# schematic.net
KiCad netlist of a schematic drawn in EAGLE
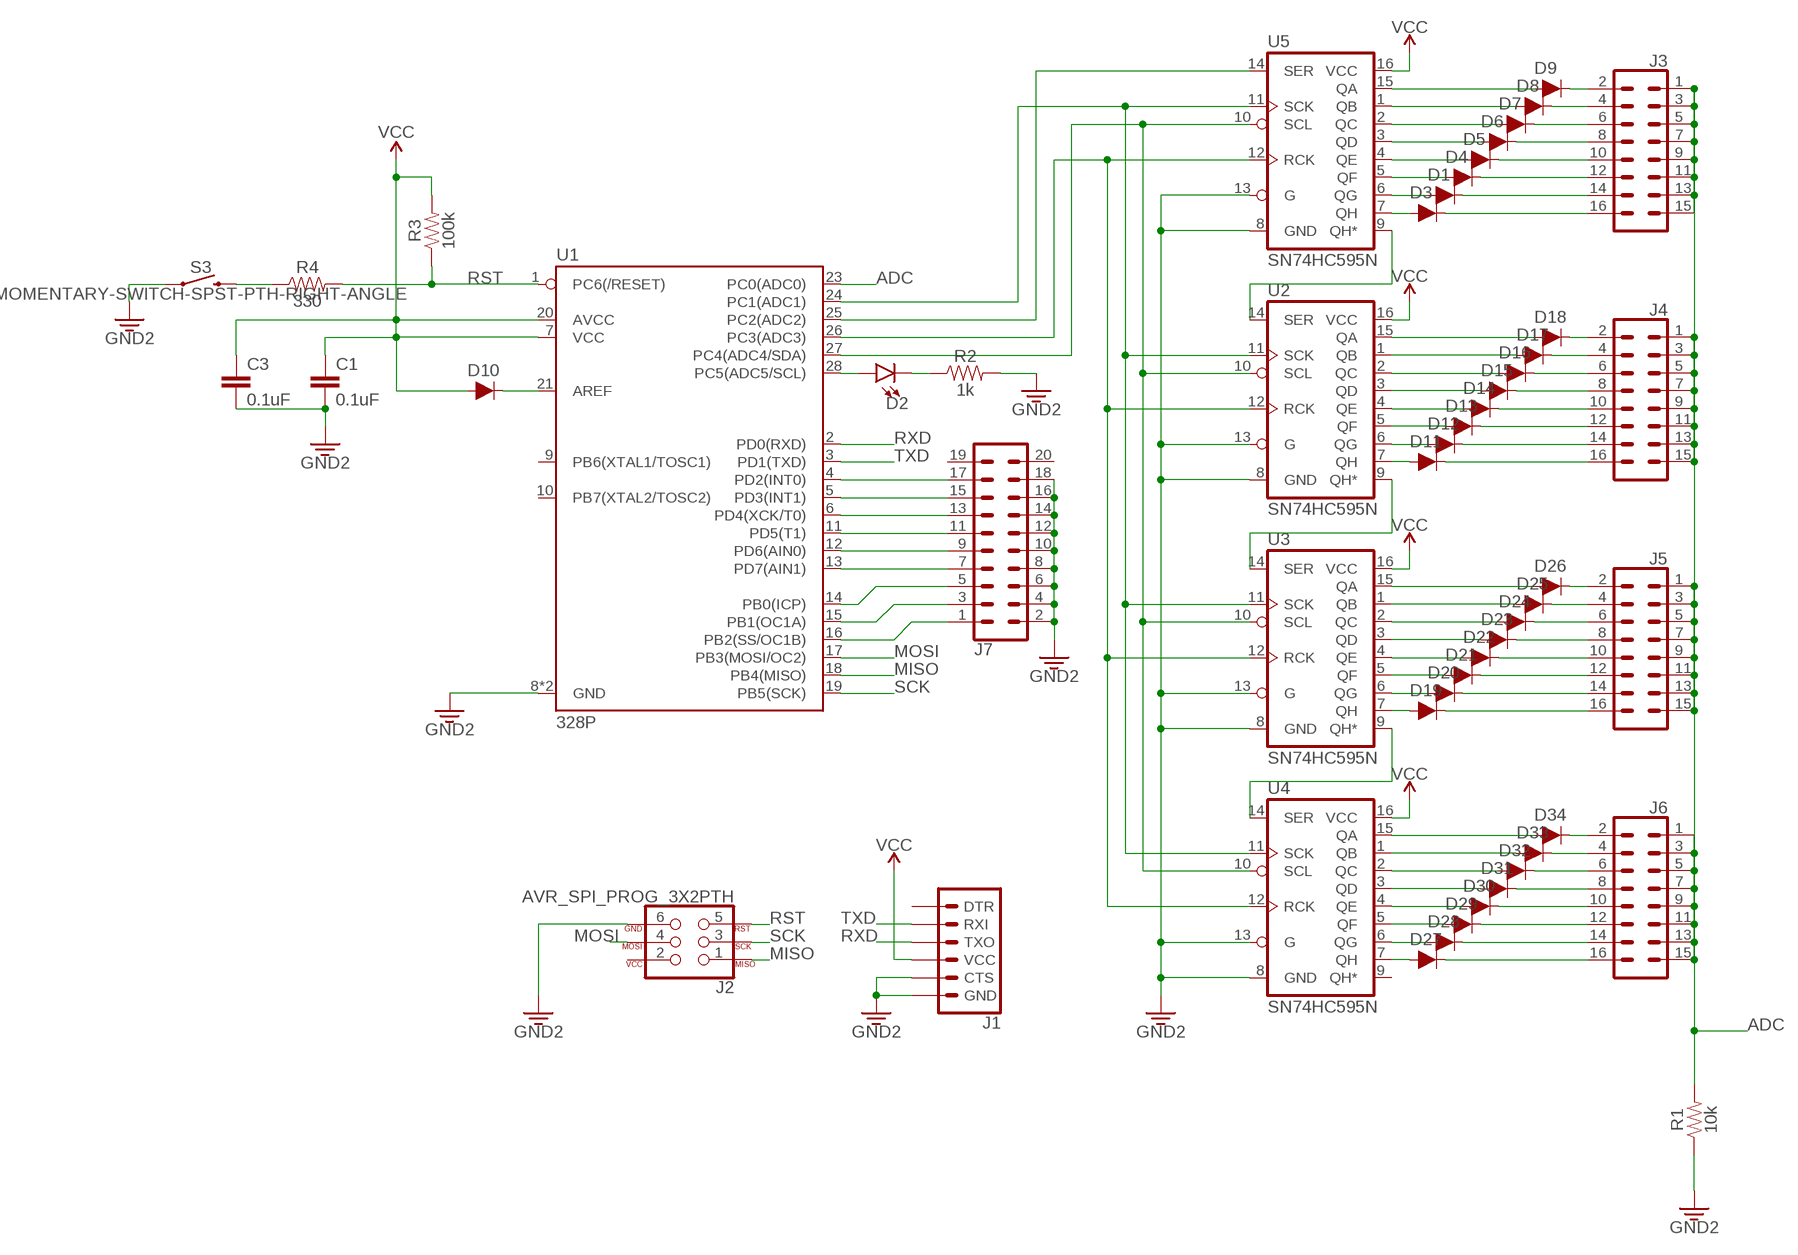
[diagram p0: schematic, sheet 1]

(export (version "E")
  (design (tool "Eeschema 10.0.6"))
  (components
    (comp (ref "C1")
      (value "0.1uF")
      (footprint "eagle-import:CAP-PTH-SMALL-KIT")
      (libsource (lib "eagle-import") (part "0.1UF-KIT-EZ-50V-20%"))
    )
    (comp (ref "C3")
      (value "0.1uF")
      (footprint "eagle-import:CAP-PTH-SMALL-KIT")
      (libsource (lib "eagle-import") (part "0.1UF-KIT-EZ-50V-20%"))
    )
    (comp (ref "D1")
      (value "200mA/100V/1V")
      (footprint "eagle-import:DIODE-1N4148")
      (libsource (lib "eagle-import") (part "DIODE-1N4148"))
    )
    (comp (ref "D2")
      (value "LED5MM")
      (footprint "eagle-import:LED_5MM")
      (libsource (lib "eagle-import") (part "LED5MM"))
    )
    (comp (ref "D3")
      (value "200mA/100V/1V")
      (footprint "eagle-import:DIODE-1N4148")
      (libsource (lib "eagle-import") (part "DIODE-1N4148"))
    )
    (comp (ref "D4")
      (value "200mA/100V/1V")
      (footprint "eagle-import:DIODE-1N4148")
      (libsource (lib "eagle-import") (part "DIODE-1N4148"))
    )
    (comp (ref "D5")
      (value "200mA/100V/1V")
      (footprint "eagle-import:DIODE-1N4148")
      (libsource (lib "eagle-import") (part "DIODE-1N4148"))
    )
    (comp (ref "D6")
      (value "200mA/100V/1V")
      (footprint "eagle-import:DIODE-1N4148")
      (libsource (lib "eagle-import") (part "DIODE-1N4148"))
    )
    (comp (ref "D7")
      (value "200mA/100V/1V")
      (footprint "eagle-import:DIODE-1N4148")
      (libsource (lib "eagle-import") (part "DIODE-1N4148"))
    )
    (comp (ref "D8")
      (value "200mA/100V/1V")
      (footprint "eagle-import:DIODE-1N4148")
      (libsource (lib "eagle-import") (part "DIODE-1N4148"))
    )
    (comp (ref "D9")
      (value "200mA/100V/1V")
      (footprint "eagle-import:DIODE-1N4148")
      (libsource (lib "eagle-import") (part "DIODE-1N4148"))
    )
    (comp (ref "D10")
      (value "200mA/100V/1V")
      (footprint "eagle-import:DIODE-1N4148")
      (libsource (lib "eagle-import") (part "DIODE-1N4148"))
    )
    (comp (ref "D11")
      (value "200mA/100V/1V")
      (footprint "eagle-import:DIODE-1N4148")
      (libsource (lib "eagle-import") (part "DIODE-1N4148"))
    )
    (comp (ref "D12")
      (value "200mA/100V/1V")
      (footprint "eagle-import:DIODE-1N4148")
      (libsource (lib "eagle-import") (part "DIODE-1N4148"))
    )
    (comp (ref "D13")
      (value "200mA/100V/1V")
      (footprint "eagle-import:DIODE-1N4148")
      (libsource (lib "eagle-import") (part "DIODE-1N4148"))
    )
    (comp (ref "D14")
      (value "200mA/100V/1V")
      (footprint "eagle-import:DIODE-1N4148")
      (libsource (lib "eagle-import") (part "DIODE-1N4148"))
    )
    (comp (ref "D15")
      (value "200mA/100V/1V")
      (footprint "eagle-import:DIODE-1N4148")
      (libsource (lib "eagle-import") (part "DIODE-1N4148"))
    )
    (comp (ref "D16")
      (value "200mA/100V/1V")
      (footprint "eagle-import:DIODE-1N4148")
      (libsource (lib "eagle-import") (part "DIODE-1N4148"))
    )
    (comp (ref "D17")
      (value "200mA/100V/1V")
      (footprint "eagle-import:DIODE-1N4148")
      (libsource (lib "eagle-import") (part "DIODE-1N4148"))
    )
    (comp (ref "D18")
      (value "200mA/100V/1V")
      (footprint "eagle-import:DIODE-1N4148")
      (libsource (lib "eagle-import") (part "DIODE-1N4148"))
    )
    (comp (ref "D19")
      (value "200mA/100V/1V")
      (footprint "eagle-import:DIODE-1N4148")
      (libsource (lib "eagle-import") (part "DIODE-1N4148"))
    )
    (comp (ref "D20")
      (value "200mA/100V/1V")
      (footprint "eagle-import:DIODE-1N4148")
      (libsource (lib "eagle-import") (part "DIODE-1N4148"))
    )
    (comp (ref "D21")
      (value "200mA/100V/1V")
      (footprint "eagle-import:DIODE-1N4148")
      (libsource (lib "eagle-import") (part "DIODE-1N4148"))
    )
    (comp (ref "D22")
      (value "200mA/100V/1V")
      (footprint "eagle-import:DIODE-1N4148")
      (libsource (lib "eagle-import") (part "DIODE-1N4148"))
    )
    (comp (ref "D23")
      (value "200mA/100V/1V")
      (footprint "eagle-import:DIODE-1N4148")
      (libsource (lib "eagle-import") (part "DIODE-1N4148"))
    )
    (comp (ref "D24")
      (value "200mA/100V/1V")
      (footprint "eagle-import:DIODE-1N4148")
      (libsource (lib "eagle-import") (part "DIODE-1N4148"))
    )
    (comp (ref "D25")
      (value "200mA/100V/1V")
      (footprint "eagle-import:DIODE-1N4148")
      (libsource (lib "eagle-import") (part "DIODE-1N4148"))
    )
    (comp (ref "D26")
      (value "200mA/100V/1V")
      (footprint "eagle-import:DIODE-1N4148")
      (libsource (lib "eagle-import") (part "DIODE-1N4148"))
    )
    (comp (ref "D27")
      (value "200mA/100V/1V")
      (footprint "eagle-import:DIODE-1N4148")
      (libsource (lib "eagle-import") (part "DIODE-1N4148"))
    )
    (comp (ref "D28")
      (value "200mA/100V/1V")
      (footprint "eagle-import:DIODE-1N4148")
      (libsource (lib "eagle-import") (part "DIODE-1N4148"))
    )
    (comp (ref "D29")
      (value "200mA/100V/1V")
      (footprint "eagle-import:DIODE-1N4148")
      (libsource (lib "eagle-import") (part "DIODE-1N4148"))
    )
    (comp (ref "D30")
      (value "200mA/100V/1V")
      (footprint "eagle-import:DIODE-1N4148")
      (libsource (lib "eagle-import") (part "DIODE-1N4148"))
    )
    (comp (ref "D31")
      (value "200mA/100V/1V")
      (footprint "eagle-import:DIODE-1N4148")
      (libsource (lib "eagle-import") (part "DIODE-1N4148"))
    )
    (comp (ref "D32")
      (value "200mA/100V/1V")
      (footprint "eagle-import:DIODE-1N4148")
      (libsource (lib "eagle-import") (part "DIODE-1N4148"))
    )
    (comp (ref "D33")
      (value "200mA/100V/1V")
      (footprint "eagle-import:DIODE-1N4148")
      (libsource (lib "eagle-import") (part "DIODE-1N4148"))
    )
    (comp (ref "D34")
      (value "200mA/100V/1V")
      (footprint "eagle-import:DIODE-1N4148")
      (libsource (lib "eagle-import") (part "DIODE-1N4148"))
    )
    (comp (ref "J1")
      (value "6_PIN_SERIAL_TARGETLOCK")
      (footprint "eagle-import:1X06_LOCK")
      (libsource (lib "eagle-import") (part "6_PIN_SERIAL_TARGETLOCK"))
    )
    (comp (ref "J2")
      (value "AVR_SPI_PROG_3X2PTH")
      (footprint "eagle-import:2X3")
      (libsource (lib "eagle-import") (part "AVR_SPI_PROG_3X2PTH"))
    )
    (comp (ref "J3")
      (value "CONN_08X2_HEADER")
      (footprint "eagle-import:2X8")
      (libsource (lib "eagle-import") (part "CONN_08X2_HEADER"))
    )
    (comp (ref "J4")
      (value "CONN_08X2_HEADER")
      (footprint "eagle-import:2X8")
      (libsource (lib "eagle-import") (part "CONN_08X2_HEADER"))
    )
    (comp (ref "J5")
      (value "CONN_08X2_HEADER")
      (footprint "eagle-import:2X8")
      (libsource (lib "eagle-import") (part "CONN_08X2_HEADER"))
    )
    (comp (ref "J6")
      (value "CONN_08X2_HEADER")
      (footprint "eagle-import:2X8")
      (libsource (lib "eagle-import") (part "CONN_08X2_HEADER"))
    )
    (comp (ref "J7")
      (value "CONN_10X2")
      (footprint "eagle-import:2X10")
      (libsource (lib "eagle-import") (part "CONN_10X2"))
    )
    (comp (ref "R1")
      (value "10k")
      (footprint "eagle-import:AXIAL-0.3")
      (libsource (lib "eagle-import") (part "10KOHM-HORIZ-1/4W-1%"))
    )
    (comp (ref "R2")
      (value "1k")
      (footprint "eagle-import:AXIAL-0.3")
      (libsource (lib "eagle-import") (part "1KOHM-HORIZ-1/4W-1%"))
    )
    (comp (ref "R3")
      (value "100k")
      (footprint "eagle-import:AXIAL-0.3")
      (libsource (lib "eagle-import") (part "100KOHM-HORIZ-1/4W-5%"))
    )
    (comp (ref "R4")
      (value "330")
      (footprint "eagle-import:AXIAL-0.3")
      (libsource (lib "eagle-import") (part "1KOHM-HORIZ-1/4W-1%"))
    )
    (comp (ref "S3")
      (value "MOMENTARY-SWITCH-SPST-PTH-RIGHT-ANGLE")
      (footprint "eagle-import:TACTILE_SWITCH_PTH_RIGHT_ANGLE")
      (libsource (lib "eagle-import") (part "MOMENTARY-SWITCH-SPST-PTH-RIGHT-ANGLE"))
    )
    (comp (ref "U1")
      (value "328P")
      (footprint "eagle-import:DIP28")
      (libsource (lib "eagle-import") (part "ATMEGA328P_PDIP"))
    )
    (comp (ref "U2")
      (value "SN74HC595N")
      (footprint "eagle-import:DIP16")
      (libsource (lib "eagle-import") (part "74595NHC"))
    )
    (comp (ref "U3")
      (value "SN74HC595N")
      (footprint "eagle-import:DIP16")
      (libsource (lib "eagle-import") (part "74595NHC"))
    )
    (comp (ref "U4")
      (value "SN74HC595N")
      (footprint "eagle-import:DIP16")
      (libsource (lib "eagle-import") (part "74595NHC"))
    )
    (comp (ref "U5")
      (value "SN74HC595N")
      (footprint "eagle-import:DIP16")
      (libsource (lib "eagle-import") (part "74595NHC"))
    )
  )
  (nets
    (net (code "1") (name "/ADC") (class "Default")
      (node (ref "J3") (pin "1") (pinfunction "1_1") (pintype "passive"))
      (node (ref "J3") (pin "11") (pinfunction "11_11") (pintype "passive"))
      (node (ref "J3") (pin "13") (pinfunction "13_13") (pintype "passive"))
      (node (ref "J3") (pin "15") (pinfunction "15_15") (pintype "passive"))
      (node (ref "J3") (pin "3") (pinfunction "3_3") (pintype "passive"))
      (node (ref "J3") (pin "5") (pinfunction "5_5") (pintype "passive"))
      (node (ref "J3") (pin "7") (pinfunction "7_7") (pintype "passive"))
      (node (ref "J3") (pin "9") (pinfunction "9_9") (pintype "passive"))
      (node (ref "J4") (pin "1") (pinfunction "1_1") (pintype "passive"))
      (node (ref "J4") (pin "11") (pinfunction "11_11") (pintype "passive"))
      (node (ref "J4") (pin "13") (pinfunction "13_13") (pintype "passive"))
      (node (ref "J4") (pin "15") (pinfunction "15_15") (pintype "passive"))
      (node (ref "J4") (pin "3") (pinfunction "3_3") (pintype "passive"))
      (node (ref "J4") (pin "5") (pinfunction "5_5") (pintype "passive"))
      (node (ref "J4") (pin "7") (pinfunction "7_7") (pintype "passive"))
      (node (ref "J4") (pin "9") (pinfunction "9_9") (pintype "passive"))
      (node (ref "J5") (pin "1") (pinfunction "1_1") (pintype "passive"))
      (node (ref "J5") (pin "11") (pinfunction "11_11") (pintype "passive"))
      (node (ref "J5") (pin "13") (pinfunction "13_13") (pintype "passive"))
      (node (ref "J5") (pin "15") (pinfunction "15_15") (pintype "passive"))
      (node (ref "J5") (pin "3") (pinfunction "3_3") (pintype "passive"))
      (node (ref "J5") (pin "5") (pinfunction "5_5") (pintype "passive"))
      (node (ref "J5") (pin "7") (pinfunction "7_7") (pintype "passive"))
      (node (ref "J5") (pin "9") (pinfunction "9_9") (pintype "passive"))
      (node (ref "J6") (pin "1") (pinfunction "1_1") (pintype "passive"))
      (node (ref "J6") (pin "11") (pinfunction "11_11") (pintype "passive"))
      (node (ref "J6") (pin "13") (pinfunction "13_13") (pintype "passive"))
      (node (ref "J6") (pin "15") (pinfunction "15_15") (pintype "passive"))
      (node (ref "J6") (pin "3") (pinfunction "3_3") (pintype "passive"))
      (node (ref "J6") (pin "5") (pinfunction "5_5") (pintype "passive"))
      (node (ref "J6") (pin "7") (pinfunction "7_7") (pintype "passive"))
      (node (ref "J6") (pin "9") (pinfunction "9_9") (pintype "passive"))
      (node (ref "R1") (pin "P$2") (pinfunction "2_P$2") (pintype "passive"))
      (node (ref "U1") (pin "23") (pinfunction "PC0(ADC0)_23") (pintype "bidirectional"))
    )
    (net (code "2") (name "/MISO") (class "Default")
      (node (ref "J2") (pin "1") (pinfunction "1_1") (pintype "passive"))
      (node (ref "U1") (pin "18") (pinfunction "PB4(MISO)_18") (pintype "bidirectional"))
    )
    (net (code "3") (name "/MOSI") (class "Default")
      (node (ref "J2") (pin "4") (pinfunction "4_4") (pintype "passive"))
      (node (ref "U1") (pin "17") (pinfunction "PB3(MOSI/OC2)_17") (pintype "bidirectional"))
    )
    (net (code "4") (name "/RST") (class "Default")
      (node (ref "J2") (pin "5") (pinfunction "5_5") (pintype "passive"))
      (node (ref "R3") (pin "P$1") (pinfunction "1_P$1") (pintype "passive"))
      (node (ref "R4") (pin "P$2") (pinfunction "2_P$2") (pintype "passive"))
      (node (ref "U1") (pin "1") (pinfunction "PC6(/RESET)_1") (pintype "bidirectional"))
    )
    (net (code "5") (name "/RXD") (class "Default")
      (node (ref "J1") (pin "3") (pinfunction "TXO_3") (pintype "passive"))
      (node (ref "U1") (pin "2") (pinfunction "PD0(RXD)_2") (pintype "bidirectional"))
    )
    (net (code "6") (name "/SCK") (class "Default")
      (node (ref "J2") (pin "3") (pinfunction "3_3") (pintype "passive"))
      (node (ref "U1") (pin "19") (pinfunction "PB5(SCK)_19") (pintype "bidirectional"))
    )
    (net (code "7") (name "/TXD") (class "Default")
      (node (ref "J1") (pin "2") (pinfunction "RXI_2") (pintype "passive"))
      (node (ref "U1") (pin "3") (pinfunction "PD1(TXD)_3") (pintype "bidirectional"))
    )
    (net (code "8") (name "GND2") (class "Default")
      (node (ref "C1") (pin "2") (pinfunction "2_2") (pintype "passive"))
      (node (ref "C3") (pin "2") (pinfunction "2_2") (pintype "passive"))
      (node (ref "J1") (pin "5") (pinfunction "CTS_5") (pintype "passive"))
      (node (ref "J1") (pin "6") (pinfunction "GND_6") (pintype "passive"))
      (node (ref "J2") (pin "6") (pinfunction "6_6") (pintype "passive"))
      (node (ref "J7") (pin "10") (pinfunction "10_10") (pintype "passive"))
      (node (ref "J7") (pin "12") (pinfunction "12_12") (pintype "passive"))
      (node (ref "J7") (pin "14") (pinfunction "14_14") (pintype "passive"))
      (node (ref "J7") (pin "16") (pinfunction "16_16") (pintype "passive"))
      (node (ref "J7") (pin "18") (pinfunction "18_18") (pintype "passive"))
      (node (ref "J7") (pin "2") (pinfunction "2_2") (pintype "passive"))
      (node (ref "J7") (pin "4") (pinfunction "4_4") (pintype "passive"))
      (node (ref "J7") (pin "6") (pinfunction "6_6") (pintype "passive"))
      (node (ref "J7") (pin "8") (pinfunction "8_8") (pintype "passive"))
      (node (ref "R1") (pin "P$1") (pinfunction "1_P$1") (pintype "passive"))
      (node (ref "R2") (pin "P$2") (pinfunction "2_P$2") (pintype "passive"))
      (node (ref "S3") (pin "1") (pinfunction "1_1") (pintype "passive"))
      (node (ref "U1") (pin "22") (pinfunction "GND_22") (pintype "bidirectional"))
      (node (ref "U1") (pin "8") (pinfunction "GND_8") (pintype "bidirectional"))
      (node (ref "U2") (pin "13") (pinfunction "G_13") (pintype "input"))
      (node (ref "U2") (pin "8") (pinfunction "GND_8") (pintype "power_in"))
      (node (ref "U3") (pin "13") (pinfunction "G_13") (pintype "input"))
      (node (ref "U3") (pin "8") (pinfunction "GND_8") (pintype "power_in"))
      (node (ref "U4") (pin "13") (pinfunction "G_13") (pintype "input"))
      (node (ref "U4") (pin "8") (pinfunction "GND_8") (pintype "power_in"))
      (node (ref "U5") (pin "13") (pinfunction "G_13") (pintype "input"))
      (node (ref "U5") (pin "8") (pinfunction "GND_8") (pintype "power_in"))
    )
    (net (code "9") (name "Net-(D1-PadC)") (class "Default")
      (node (ref "D1") (pin "C") (pinfunction "C_C") (pintype "passive"))
      (node (ref "J3") (pin "14") (pinfunction "14_14") (pintype "passive"))
    )
    (net (code "10") (name "Net-(D2-C)") (class "Default")
      (node (ref "D2") (pin "K") (pinfunction "C_K") (pintype "passive"))
      (node (ref "R2") (pin "P$1") (pinfunction "1_P$1") (pintype "passive"))
    )
    (net (code "11") (name "Net-(D3-PadC)") (class "Default")
      (node (ref "D3") (pin "C") (pinfunction "C_C") (pintype "passive"))
      (node (ref "J3") (pin "16") (pinfunction "16_16") (pintype "passive"))
    )
    (net (code "12") (name "Net-(D4-PadC)") (class "Default")
      (node (ref "D4") (pin "C") (pinfunction "C_C") (pintype "passive"))
      (node (ref "J3") (pin "12") (pinfunction "12_12") (pintype "passive"))
    )
    (net (code "13") (name "Net-(D5-PadC)") (class "Default")
      (node (ref "D5") (pin "C") (pinfunction "C_C") (pintype "passive"))
      (node (ref "J3") (pin "10") (pinfunction "10_10") (pintype "passive"))
    )
    (net (code "14") (name "Net-(D6-PadC)") (class "Default")
      (node (ref "D6") (pin "C") (pinfunction "C_C") (pintype "passive"))
      (node (ref "J3") (pin "8") (pinfunction "8_8") (pintype "passive"))
    )
    (net (code "15") (name "Net-(D7-PadC)") (class "Default")
      (node (ref "D7") (pin "C") (pinfunction "C_C") (pintype "passive"))
      (node (ref "J3") (pin "6") (pinfunction "6_6") (pintype "passive"))
    )
    (net (code "16") (name "Net-(D8-PadC)") (class "Default")
      (node (ref "D8") (pin "C") (pinfunction "C_C") (pintype "passive"))
      (node (ref "J3") (pin "4") (pinfunction "4_4") (pintype "passive"))
    )
    (net (code "17") (name "Net-(D9-PadC)") (class "Default")
      (node (ref "D9") (pin "C") (pinfunction "C_C") (pintype "passive"))
      (node (ref "J3") (pin "2") (pinfunction "2_2") (pintype "passive"))
    )
    (net (code "18") (name "Net-(D11-PadC)") (class "Default")
      (node (ref "D11") (pin "C") (pinfunction "C_C") (pintype "passive"))
      (node (ref "J4") (pin "16") (pinfunction "16_16") (pintype "passive"))
    )
    (net (code "19") (name "Net-(D12-PadC)") (class "Default")
      (node (ref "D12") (pin "C") (pinfunction "C_C") (pintype "passive"))
      (node (ref "J4") (pin "14") (pinfunction "14_14") (pintype "passive"))
    )
    (net (code "20") (name "Net-(D13-PadC)") (class "Default")
      (node (ref "D13") (pin "C") (pinfunction "C_C") (pintype "passive"))
      (node (ref "J4") (pin "12") (pinfunction "12_12") (pintype "passive"))
    )
    (net (code "21") (name "Net-(D14-PadC)") (class "Default")
      (node (ref "D14") (pin "C") (pinfunction "C_C") (pintype "passive"))
      (node (ref "J4") (pin "10") (pinfunction "10_10") (pintype "passive"))
    )
    (net (code "22") (name "Net-(D15-PadC)") (class "Default")
      (node (ref "D15") (pin "C") (pinfunction "C_C") (pintype "passive"))
      (node (ref "J4") (pin "8") (pinfunction "8_8") (pintype "passive"))
    )
    (net (code "23") (name "Net-(D16-PadC)") (class "Default")
      (node (ref "D16") (pin "C") (pinfunction "C_C") (pintype "passive"))
      (node (ref "J4") (pin "6") (pinfunction "6_6") (pintype "passive"))
    )
    (net (code "24") (name "Net-(D17-PadC)") (class "Default")
      (node (ref "D17") (pin "C") (pinfunction "C_C") (pintype "passive"))
      (node (ref "J4") (pin "4") (pinfunction "4_4") (pintype "passive"))
    )
    (net (code "25") (name "Net-(D18-PadC)") (class "Default")
      (node (ref "D18") (pin "C") (pinfunction "C_C") (pintype "passive"))
      (node (ref "J4") (pin "2") (pinfunction "2_2") (pintype "passive"))
    )
    (net (code "26") (name "Net-(D19-PadC)") (class "Default")
      (node (ref "D19") (pin "C") (pinfunction "C_C") (pintype "passive"))
      (node (ref "J5") (pin "16") (pinfunction "16_16") (pintype "passive"))
    )
    (net (code "27") (name "Net-(D20-PadC)") (class "Default")
      (node (ref "D20") (pin "C") (pinfunction "C_C") (pintype "passive"))
      (node (ref "J5") (pin "14") (pinfunction "14_14") (pintype "passive"))
    )
    (net (code "28") (name "Net-(D21-PadC)") (class "Default")
      (node (ref "D21") (pin "C") (pinfunction "C_C") (pintype "passive"))
      (node (ref "J5") (pin "12") (pinfunction "12_12") (pintype "passive"))
    )
    (net (code "29") (name "Net-(D22-PadC)") (class "Default")
      (node (ref "D22") (pin "C") (pinfunction "C_C") (pintype "passive"))
      (node (ref "J5") (pin "10") (pinfunction "10_10") (pintype "passive"))
    )
    (net (code "30") (name "Net-(D23-PadC)") (class "Default")
      (node (ref "D23") (pin "C") (pinfunction "C_C") (pintype "passive"))
      (node (ref "J5") (pin "8") (pinfunction "8_8") (pintype "passive"))
    )
    (net (code "31") (name "Net-(D24-PadC)") (class "Default")
      (node (ref "D24") (pin "C") (pinfunction "C_C") (pintype "passive"))
      (node (ref "J5") (pin "6") (pinfunction "6_6") (pintype "passive"))
    )
    (net (code "32") (name "Net-(D25-PadC)") (class "Default")
      (node (ref "D25") (pin "C") (pinfunction "C_C") (pintype "passive"))
      (node (ref "J5") (pin "4") (pinfunction "4_4") (pintype "passive"))
    )
    (net (code "33") (name "Net-(D26-PadC)") (class "Default")
      (node (ref "D26") (pin "C") (pinfunction "C_C") (pintype "passive"))
      (node (ref "J5") (pin "2") (pinfunction "2_2") (pintype "passive"))
    )
    (net (code "34") (name "Net-(D27-PadC)") (class "Default")
      (node (ref "D27") (pin "C") (pinfunction "C_C") (pintype "passive"))
      (node (ref "J6") (pin "16") (pinfunction "16_16") (pintype "passive"))
    )
    (net (code "35") (name "Net-(D28-PadC)") (class "Default")
      (node (ref "D28") (pin "C") (pinfunction "C_C") (pintype "passive"))
      (node (ref "J6") (pin "14") (pinfunction "14_14") (pintype "passive"))
    )
    (net (code "36") (name "Net-(D29-PadC)") (class "Default")
      (node (ref "D29") (pin "C") (pinfunction "C_C") (pintype "passive"))
      (node (ref "J6") (pin "12") (pinfunction "12_12") (pintype "passive"))
    )
    (net (code "37") (name "Net-(D30-PadC)") (class "Default")
      (node (ref "D30") (pin "C") (pinfunction "C_C") (pintype "passive"))
      (node (ref "J6") (pin "10") (pinfunction "10_10") (pintype "passive"))
    )
    (net (code "38") (name "Net-(D31-PadC)") (class "Default")
      (node (ref "D31") (pin "C") (pinfunction "C_C") (pintype "passive"))
      (node (ref "J6") (pin "8") (pinfunction "8_8") (pintype "passive"))
    )
    (net (code "39") (name "Net-(D32-PadC)") (class "Default")
      (node (ref "D32") (pin "C") (pinfunction "C_C") (pintype "passive"))
      (node (ref "J6") (pin "6") (pinfunction "6_6") (pintype "passive"))
    )
    (net (code "40") (name "Net-(D33-PadC)") (class "Default")
      (node (ref "D33") (pin "C") (pinfunction "C_C") (pintype "passive"))
      (node (ref "J6") (pin "4") (pinfunction "4_4") (pintype "passive"))
    )
    (net (code "41") (name "Net-(D34-PadC)") (class "Default")
      (node (ref "D34") (pin "C") (pinfunction "C_C") (pintype "passive"))
      (node (ref "J6") (pin "2") (pinfunction "2_2") (pintype "passive"))
    )
    (net (code "42") (name "Net-(R4-1)") (class "Default")
      (node (ref "R4") (pin "P$1") (pinfunction "1_P$1") (pintype "passive"))
      (node (ref "S3") (pin "2") (pinfunction "2_2") (pintype "passive"))
    )
    (net (code "43") (name "Net-(U1-AREF)") (class "Default")
      (node (ref "D10") (pin "C") (pinfunction "C_C") (pintype "passive"))
      (node (ref "U1") (pin "21") (pinfunction "AREF_21") (pintype "bidirectional"))
    )
    (net (code "44") (name "Net-(U1-PB0(ICP))") (class "Default")
      (node (ref "J7") (pin "5") (pinfunction "5_5") (pintype "passive"))
      (node (ref "U1") (pin "14") (pinfunction "PB0(ICP)_14") (pintype "bidirectional"))
    )
    (net (code "45") (name "Net-(U1-PB1(OC1A))") (class "Default")
      (node (ref "J7") (pin "3") (pinfunction "3_3") (pintype "passive"))
      (node (ref "U1") (pin "15") (pinfunction "PB1(OC1A)_15") (pintype "bidirectional"))
    )
    (net (code "46") (name "Net-(U1-PB2(SS{slash}OC1B))") (class "Default")
      (node (ref "J7") (pin "1") (pinfunction "1_1") (pintype "passive"))
      (node (ref "U1") (pin "16") (pinfunction "PB2(SS/OC1B)_16") (pintype "bidirectional"))
    )
    (net (code "47") (name "Net-(U1-PC1(ADC1))") (class "Default")
      (node (ref "U1") (pin "24") (pinfunction "PC1(ADC1)_24") (pintype "bidirectional"))
      (node (ref "U2") (pin "11") (pinfunction "SCK_11") (pintype "input"))
      (node (ref "U3") (pin "11") (pinfunction "SCK_11") (pintype "input"))
      (node (ref "U4") (pin "11") (pinfunction "SCK_11") (pintype "input"))
      (node (ref "U5") (pin "11") (pinfunction "SCK_11") (pintype "input"))
    )
    (net (code "48") (name "Net-(U1-PC2(ADC2))") (class "Default")
      (node (ref "U1") (pin "25") (pinfunction "PC2(ADC2)_25") (pintype "bidirectional"))
      (node (ref "U5") (pin "14") (pinfunction "SER_14") (pintype "input"))
    )
    (net (code "49") (name "Net-(U1-PC3(ADC3))") (class "Default")
      (node (ref "U1") (pin "26") (pinfunction "PC3(ADC3)_26") (pintype "bidirectional"))
      (node (ref "U2") (pin "12") (pinfunction "RCK_12") (pintype "input"))
      (node (ref "U3") (pin "12") (pinfunction "RCK_12") (pintype "input"))
      (node (ref "U4") (pin "12") (pinfunction "RCK_12") (pintype "input"))
      (node (ref "U5") (pin "12") (pinfunction "RCK_12") (pintype "input"))
    )
    (net (code "50") (name "Net-(U1-PC4(ADC4{slash}SDA))") (class "Default")
      (node (ref "U1") (pin "27") (pinfunction "PC4(ADC4/SDA)_27") (pintype "bidirectional"))
      (node (ref "U2") (pin "10") (pinfunction "SCL_10") (pintype "input"))
      (node (ref "U3") (pin "10") (pinfunction "SCL_10") (pintype "input"))
      (node (ref "U4") (pin "10") (pinfunction "SCL_10") (pintype "input"))
      (node (ref "U5") (pin "10") (pinfunction "SCL_10") (pintype "input"))
    )
    (net (code "51") (name "Net-(U1-PC5(ADC5{slash}SCL))") (class "Default")
      (node (ref "D2") (pin "A") (pinfunction "A_A") (pintype "passive"))
      (node (ref "U1") (pin "28") (pinfunction "PC5(ADC5/SCL)_28") (pintype "bidirectional"))
    )
    (net (code "52") (name "Net-(U1-PD2(INT0))") (class "Default")
      (node (ref "J7") (pin "17") (pinfunction "17_17") (pintype "passive"))
      (node (ref "U1") (pin "4") (pinfunction "PD2(INT0)_4") (pintype "bidirectional"))
    )
    (net (code "53") (name "Net-(U1-PD3(INT1))") (class "Default")
      (node (ref "J7") (pin "15") (pinfunction "15_15") (pintype "passive"))
      (node (ref "U1") (pin "5") (pinfunction "PD3(INT1)_5") (pintype "bidirectional"))
    )
    (net (code "54") (name "Net-(U1-PD4(XCK{slash}T0))") (class "Default")
      (node (ref "J7") (pin "13") (pinfunction "13_13") (pintype "passive"))
      (node (ref "U1") (pin "6") (pinfunction "PD4(XCK/T0)_6") (pintype "bidirectional"))
    )
    (net (code "55") (name "Net-(U1-PD5(T1))") (class "Default")
      (node (ref "J7") (pin "11") (pinfunction "11_11") (pintype "passive"))
      (node (ref "U1") (pin "11") (pinfunction "PD5(T1)_11") (pintype "bidirectional"))
    )
    (net (code "56") (name "Net-(U1-PD6(AIN0))") (class "Default")
      (node (ref "J7") (pin "9") (pinfunction "9_9") (pintype "passive"))
      (node (ref "U1") (pin "12") (pinfunction "PD6(AIN0)_12") (pintype "bidirectional"))
    )
    (net (code "57") (name "Net-(U1-PD7(AIN1))") (class "Default")
      (node (ref "J7") (pin "7") (pinfunction "7_7") (pintype "passive"))
      (node (ref "U1") (pin "13") (pinfunction "PD7(AIN1)_13") (pintype "bidirectional"))
    )
    (net (code "58") (name "Net-(U2-QA)") (class "Default")
      (node (ref "D18") (pin "A") (pinfunction "A_A") (pintype "passive"))
      (node (ref "U2") (pin "15") (pinfunction "QA_15") (pintype "tri_state"))
    )
    (net (code "59") (name "Net-(U2-QB)") (class "Default")
      (node (ref "D17") (pin "A") (pinfunction "A_A") (pintype "passive"))
      (node (ref "U2") (pin "1") (pinfunction "QB_1") (pintype "tri_state"))
    )
    (net (code "60") (name "Net-(U2-QC)") (class "Default")
      (node (ref "D16") (pin "A") (pinfunction "A_A") (pintype "passive"))
      (node (ref "U2") (pin "2") (pinfunction "QC_2") (pintype "tri_state"))
    )
    (net (code "61") (name "Net-(U2-QD)") (class "Default")
      (node (ref "D15") (pin "A") (pinfunction "A_A") (pintype "passive"))
      (node (ref "U2") (pin "3") (pinfunction "QD_3") (pintype "tri_state"))
    )
    (net (code "62") (name "Net-(U2-QE)") (class "Default")
      (node (ref "D14") (pin "A") (pinfunction "A_A") (pintype "passive"))
      (node (ref "U2") (pin "4") (pinfunction "QE_4") (pintype "tri_state"))
    )
    (net (code "63") (name "Net-(U2-QF)") (class "Default")
      (node (ref "D13") (pin "A") (pinfunction "A_A") (pintype "passive"))
      (node (ref "U2") (pin "5") (pinfunction "QF_5") (pintype "tri_state"))
    )
    (net (code "64") (name "Net-(U2-QG)") (class "Default")
      (node (ref "D12") (pin "A") (pinfunction "A_A") (pintype "passive"))
      (node (ref "U2") (pin "6") (pinfunction "QG_6") (pintype "tri_state"))
    )
    (net (code "65") (name "Net-(U2-QH)") (class "Default")
      (node (ref "D11") (pin "A") (pinfunction "A_A") (pintype "passive"))
      (node (ref "U2") (pin "7") (pinfunction "QH_7") (pintype "tri_state"))
    )
    (net (code "66") (name "Net-(U2-QH*)") (class "Default")
      (node (ref "U2") (pin "9") (pinfunction "QH*_9") (pintype "tri_state"))
      (node (ref "U3") (pin "14") (pinfunction "SER_14") (pintype "input"))
    )
    (net (code "67") (name "Net-(U2-SER)") (class "Default")
      (node (ref "U2") (pin "14") (pinfunction "SER_14") (pintype "input"))
      (node (ref "U5") (pin "9") (pinfunction "QH*_9") (pintype "tri_state"))
    )
    (net (code "68") (name "Net-(U3-QA)") (class "Default")
      (node (ref "D26") (pin "A") (pinfunction "A_A") (pintype "passive"))
      (node (ref "U3") (pin "15") (pinfunction "QA_15") (pintype "tri_state"))
    )
    (net (code "69") (name "Net-(U3-QB)") (class "Default")
      (node (ref "D25") (pin "A") (pinfunction "A_A") (pintype "passive"))
      (node (ref "U3") (pin "1") (pinfunction "QB_1") (pintype "tri_state"))
    )
    (net (code "70") (name "Net-(U3-QC)") (class "Default")
      (node (ref "D24") (pin "A") (pinfunction "A_A") (pintype "passive"))
      (node (ref "U3") (pin "2") (pinfunction "QC_2") (pintype "tri_state"))
    )
    (net (code "71") (name "Net-(U3-QD)") (class "Default")
      (node (ref "D23") (pin "A") (pinfunction "A_A") (pintype "passive"))
      (node (ref "U3") (pin "3") (pinfunction "QD_3") (pintype "tri_state"))
    )
    (net (code "72") (name "Net-(U3-QE)") (class "Default")
      (node (ref "D22") (pin "A") (pinfunction "A_A") (pintype "passive"))
      (node (ref "U3") (pin "4") (pinfunction "QE_4") (pintype "tri_state"))
    )
    (net (code "73") (name "Net-(U3-QF)") (class "Default")
      (node (ref "D21") (pin "A") (pinfunction "A_A") (pintype "passive"))
      (node (ref "U3") (pin "5") (pinfunction "QF_5") (pintype "tri_state"))
    )
    (net (code "74") (name "Net-(U3-QG)") (class "Default")
      (node (ref "D20") (pin "A") (pinfunction "A_A") (pintype "passive"))
      (node (ref "U3") (pin "6") (pinfunction "QG_6") (pintype "tri_state"))
    )
    (net (code "75") (name "Net-(U3-QH)") (class "Default")
      (node (ref "D19") (pin "A") (pinfunction "A_A") (pintype "passive"))
      (node (ref "U3") (pin "7") (pinfunction "QH_7") (pintype "tri_state"))
    )
    (net (code "76") (name "Net-(U3-QH*)") (class "Default")
      (node (ref "U3") (pin "9") (pinfunction "QH*_9") (pintype "tri_state"))
      (node (ref "U4") (pin "14") (pinfunction "SER_14") (pintype "input"))
    )
    (net (code "77") (name "Net-(U4-QA)") (class "Default")
      (node (ref "D34") (pin "A") (pinfunction "A_A") (pintype "passive"))
      (node (ref "U4") (pin "15") (pinfunction "QA_15") (pintype "tri_state"))
    )
    (net (code "78") (name "Net-(U4-QB)") (class "Default")
      (node (ref "D33") (pin "A") (pinfunction "A_A") (pintype "passive"))
      (node (ref "U4") (pin "1") (pinfunction "QB_1") (pintype "tri_state"))
    )
    (net (code "79") (name "Net-(U4-QC)") (class "Default")
      (node (ref "D32") (pin "A") (pinfunction "A_A") (pintype "passive"))
      (node (ref "U4") (pin "2") (pinfunction "QC_2") (pintype "tri_state"))
    )
    (net (code "80") (name "Net-(U4-QD)") (class "Default")
      (node (ref "D31") (pin "A") (pinfunction "A_A") (pintype "passive"))
      (node (ref "U4") (pin "3") (pinfunction "QD_3") (pintype "tri_state"))
    )
    (net (code "81") (name "Net-(U4-QE)") (class "Default")
      (node (ref "D30") (pin "A") (pinfunction "A_A") (pintype "passive"))
      (node (ref "U4") (pin "4") (pinfunction "QE_4") (pintype "tri_state"))
    )
    (net (code "82") (name "Net-(U4-QF)") (class "Default")
      (node (ref "D29") (pin "A") (pinfunction "A_A") (pintype "passive"))
      (node (ref "U4") (pin "5") (pinfunction "QF_5") (pintype "tri_state"))
    )
    (net (code "83") (name "Net-(U4-QG)") (class "Default")
      (node (ref "D28") (pin "A") (pinfunction "A_A") (pintype "passive"))
      (node (ref "U4") (pin "6") (pinfunction "QG_6") (pintype "tri_state"))
    )
    (net (code "84") (name "Net-(U4-QH)") (class "Default")
      (node (ref "D27") (pin "A") (pinfunction "A_A") (pintype "passive"))
      (node (ref "U4") (pin "7") (pinfunction "QH_7") (pintype "tri_state"))
    )
    (net (code "85") (name "Net-(U5-QA)") (class "Default")
      (node (ref "D9") (pin "A") (pinfunction "A_A") (pintype "passive"))
      (node (ref "U5") (pin "15") (pinfunction "QA_15") (pintype "tri_state"))
    )
    (net (code "86") (name "Net-(U5-QB)") (class "Default")
      (node (ref "D8") (pin "A") (pinfunction "A_A") (pintype "passive"))
      (node (ref "U5") (pin "1") (pinfunction "QB_1") (pintype "tri_state"))
    )
    (net (code "87") (name "Net-(U5-QC)") (class "Default")
      (node (ref "D7") (pin "A") (pinfunction "A_A") (pintype "passive"))
      (node (ref "U5") (pin "2") (pinfunction "QC_2") (pintype "tri_state"))
    )
    (net (code "88") (name "Net-(U5-QD)") (class "Default")
      (node (ref "D6") (pin "A") (pinfunction "A_A") (pintype "passive"))
      (node (ref "U5") (pin "3") (pinfunction "QD_3") (pintype "tri_state"))
    )
    (net (code "89") (name "Net-(U5-QE)") (class "Default")
      (node (ref "D5") (pin "A") (pinfunction "A_A") (pintype "passive"))
      (node (ref "U5") (pin "4") (pinfunction "QE_4") (pintype "tri_state"))
    )
    (net (code "90") (name "Net-(U5-QF)") (class "Default")
      (node (ref "D4") (pin "A") (pinfunction "A_A") (pintype "passive"))
      (node (ref "U5") (pin "5") (pinfunction "QF_5") (pintype "tri_state"))
    )
    (net (code "91") (name "Net-(U5-QG)") (class "Default")
      (node (ref "D1") (pin "A") (pinfunction "A_A") (pintype "passive"))
      (node (ref "U5") (pin "6") (pinfunction "QG_6") (pintype "tri_state"))
    )
    (net (code "92") (name "Net-(U5-QH)") (class "Default")
      (node (ref "D3") (pin "A") (pinfunction "A_A") (pintype "passive"))
      (node (ref "U5") (pin "7") (pinfunction "QH_7") (pintype "tri_state"))
    )
    (net (code "93") (name "VCC") (class "Default")
      (node (ref "C1") (pin "1") (pinfunction "1_1") (pintype "passive"))
      (node (ref "C3") (pin "1") (pinfunction "1_1") (pintype "passive"))
      (node (ref "D10") (pin "A") (pinfunction "A_A") (pintype "passive"))
      (node (ref "J1") (pin "4") (pinfunction "VCC_4") (pintype "passive"))
      (node (ref "R3") (pin "P$2") (pinfunction "2_P$2") (pintype "passive"))
      (node (ref "U1") (pin "20") (pinfunction "AVCC_20") (pintype "bidirectional"))
      (node (ref "U1") (pin "7") (pinfunction "VCC_7") (pintype "bidirectional"))
      (node (ref "U2") (pin "16") (pinfunction "VCC_16") (pintype "power_in"))
      (node (ref "U3") (pin "16") (pinfunction "VCC_16") (pintype "power_in"))
      (node (ref "U4") (pin "16") (pinfunction "VCC_16") (pintype "power_in"))
      (node (ref "U5") (pin "16") (pinfunction "VCC_16") (pintype "power_in"))
    )
    (net (code "94") (name "unconnected-(J1-DTR-Pad1)") (class "Default")
      (node (ref "J1") (pin "1") (pinfunction "DTR_1") (pintype "passive"))
    )
    (net (code "95") (name "unconnected-(J2-Pad2)") (class "Default")
      (node (ref "J2") (pin "2") (pinfunction "2_2") (pintype "passive"))
    )
    (net (code "96") (name "unconnected-(J7-Pad19)") (class "Default")
      (node (ref "J7") (pin "19") (pinfunction "19_19") (pintype "passive"))
    )
    (net (code "97") (name "unconnected-(J7-Pad20)") (class "Default")
      (node (ref "J7") (pin "20") (pinfunction "20_20") (pintype "passive"))
    )
    (net (code "98") (name "unconnected-(U1-PB6(XTAL1{slash}TOSC1)-Pad9)") (class "Default")
      (node (ref "U1") (pin "9") (pinfunction "PB6(XTAL1/TOSC1)_9") (pintype "bidirectional"))
    )
    (net (code "99") (name "unconnected-(U1-PB7(XTAL2{slash}TOSC2)-Pad10)") (class "Default")
      (node (ref "U1") (pin "10") (pinfunction "PB7(XTAL2/TOSC2)_10") (pintype "bidirectional"))
    )
    (net (code "100") (name "unconnected-(U4-QH*-Pad9)") (class "Default")
      (node (ref "U4") (pin "9") (pinfunction "QH*_9") (pintype "tri_state"))
    )
  )
)
